# Schema.net
KiCad netlist of a schematic drawn in Altium Designer
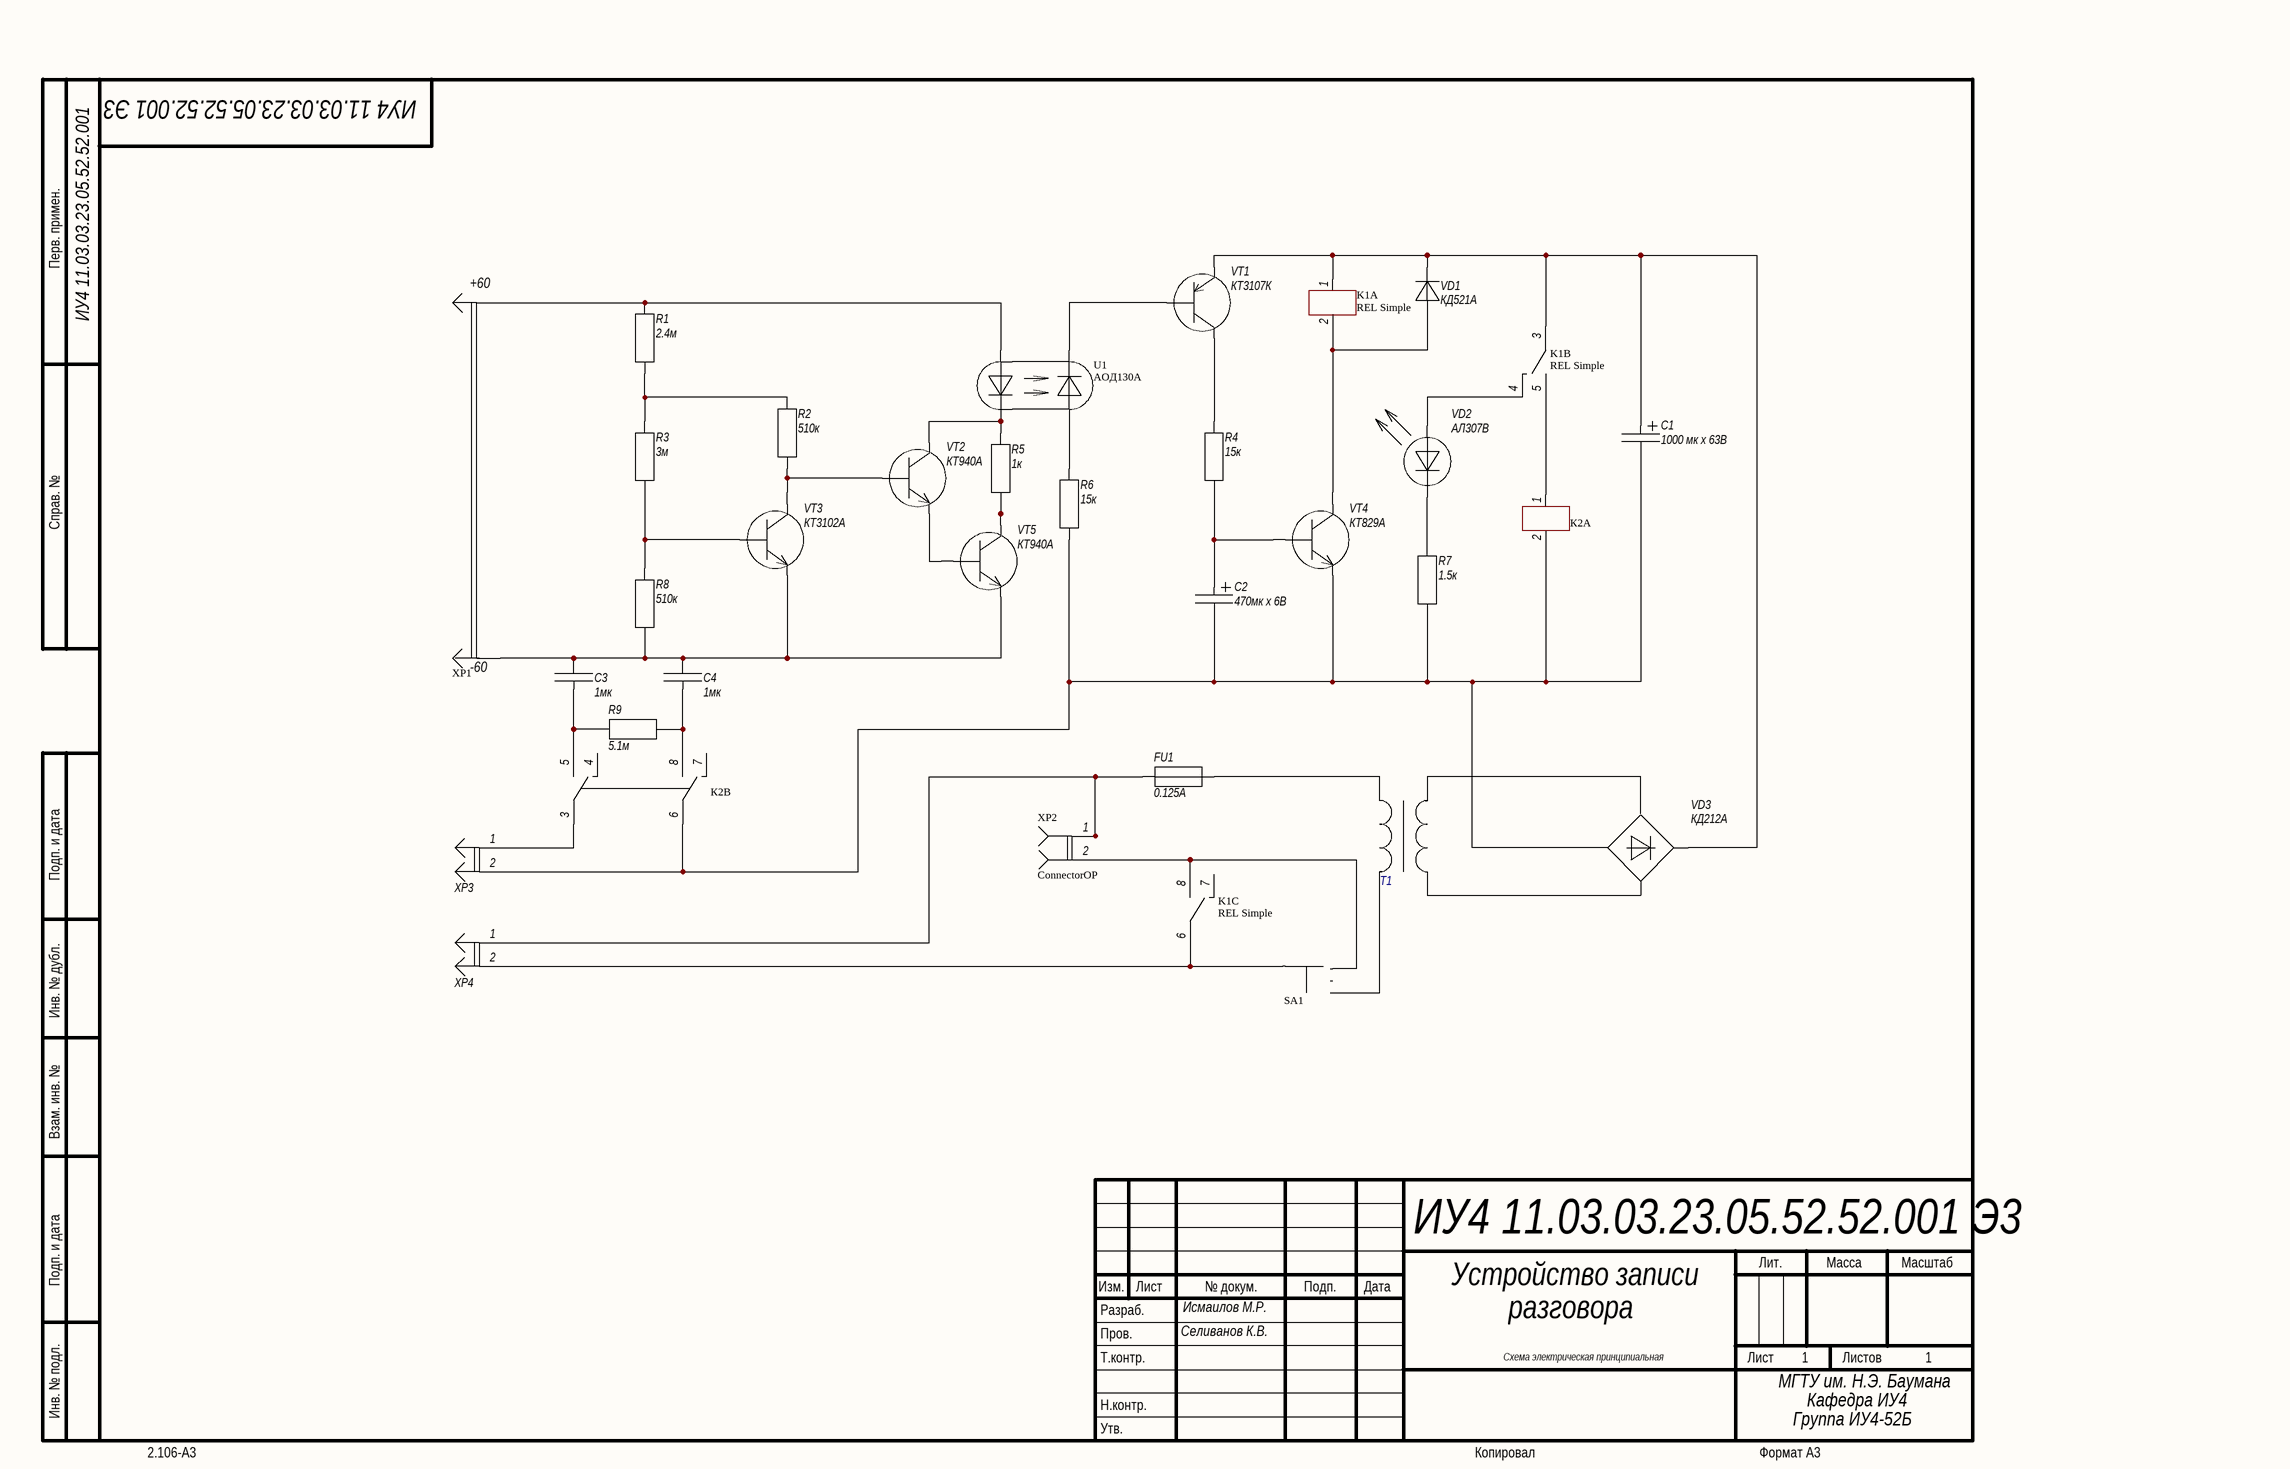
[diagram p0: Schema.SchDoc]

(export (version "E")
  (design (tool "Eeschema 10.0.6"))
  (components
    (comp (ref "C1")
      (value "1000 мк х 63В")
      (footprint "CAPPR1000-2300X4200")
      (libsource (lib "TKS Semestr") (part "CapPol 1000 мк х 63В"))
    )
    (comp (ref "C2")
      (value "470мк х 6В")
      (footprint "CAPPR1000-3600X5200")
      (libsource (lib "TKS Semestr") (part "CapPol 470мк х 6В"))
    )
    (comp (ref "C3")
      (value "1мк")
      (footprint "CAPRB_MURATA_DEBE33D103ZA3B")
      (libsource (lib "TKS Semestr") (part "Cap"))
    )
    (comp (ref "C4")
      (value "1мк")
      (footprint "CAPRB_MURATA_DEBE33D103ZA3B")
      (libsource (lib "TKS Semestr") (part "Cap"))
    )
    (comp (ref "FU1")
      (value "0.125А")
      (footprint "FUSH_SCHURTER_OGN")
      (libsource (lib "TKS Semestr") (part "Fuse 0.125А"))
    )
    (comp (ref "K1") (value "REL Simple") (footprint "USSR relay") (libsource (lib "") (part "REL Simple_1")))
    (comp (ref "R1")
      (value "2.4м")
      (footprint "RES2032-1400X350")
      (libsource (lib "TKS Semestr") (part "res 2.4м 2Вт"))
    )
    (comp (ref "R2")
      (value "510к")
      (footprint "RES2032-1400X350")
      (libsource (lib "TKS Semestr") (part "res 510к 2Вт"))
    )
    (comp (ref "R3")
      (value "3м")
      (footprint "RES2032-1400X350")
      (libsource (lib "TKS Semestr") (part "res 3м 2Вт"))
    )
    (comp (ref "R4")
      (value "15к")
      (footprint "RES2032-1400X350")
      (libsource (lib "TKS Semestr") (part "res 15к 2Вт"))
    )
    (comp (ref "R5")
      (value "1к")
      (footprint "RES2032-1400X350")
      (libsource (lib "TKS Semestr") (part "res 1к 2Вт"))
    )
    (comp (ref "R6")
      (value "15к")
      (footprint "RES2032-1400X350")
      (libsource (lib "TKS Semestr") (part "res 15к 2Вт"))
    )
    (comp (ref "R7")
      (value "1.5к")
      (footprint "RES2032-1400X350")
      (libsource (lib "TKS Semestr") (part "res 1.5к 2Вт"))
    )
    (comp (ref "R8")
      (value "510к")
      (footprint "RES2032-1400X350")
      (libsource (lib "TKS Semestr") (part "res 510к 2Вт"))
    )
    (comp (ref "R9")
      (value "5.1м")
      (footprint "RES2032-1400X350")
      (libsource (lib "TKS Semestr") (part "res 5.1м 2Вт"))
    )
    (comp (ref "SA1")
      (value "3-positoin switch")
      (footprint "SW_NR01103ANG13-1C")
      (libsource (lib "TKS Semestr") (part "3-positoin switch"))
    )
    (comp (ref "T1") (value "~") (libsource (lib "TKS Semestr") (part "TRANSFORMATOR-2")))
    (comp (ref "U1")
      (value "АОД130А")
      (footprint "DIP1016W50P254L458H480Q4")
      (libsource (lib "TKS Semestr") (part "opt АОД130А"))
    )
    (comp (ref "VD1")
      (value "КД521А")
      (footprint "DO-35")
      (libsource (lib "TKS Semestr") (part "DIODE КД521А"))
    )
    (comp (ref "VD2")
      (value "АЛ307В")
      (footprint "LED_3MM_GREEN_1C-2A")
      (libsource (lib "TKS Semestr") (part "LED АЛ307В"))
    )
    (comp (ref "VD3")
      (value "КД212А")
      (footprint "DIOB_GBJ2506")
      (libsource (lib "TKS Semestr") (part "BRIDGE"))
    )
    (comp (ref "VT1")
      (value "КТ3107К")
      (footprint "TO-92AA-P152")
      (libsource (lib "TKS Semestr") (part "КТ3107К"))
    )
    (comp (ref "VT2") (value "КТ940А") (footprint "TO-126-v") (libsource (lib "TKS Semestr") (part "КТ940А")))
    (comp (ref "VT3") (value "КТ3102А") (footprint "TO-18") (libsource (lib "TKS Semestr") (part "КТ3102А")))
    (comp (ref "VT4")
      (value "КТ829А")
      (footprint "TO-92AA-P152")
      (libsource (lib "TKS Semestr") (part "КТ829А"))
    )
    (comp (ref "VT5") (value "КТ940А") (footprint "TO-126-v") (libsource (lib "TKS Semestr") (part "КТ940А")))
    (comp (ref "XP1")
      (value "Connector2-long")
      (footprint "PHOENIX_1715721")
      (libsource (lib "TKS Semestr") (part "Connector Long"))
    )
    (comp (ref "XP2")
      (value "ConnectorOP")
      (footprint "PHOENIX_1715721")
      (libsource (lib "TKS Semestr") (part "ConnectorOP"))
    )
    (comp (ref "XP3")
      (value "~")
      (footprint "PHOENIX_1715721")
      (libsource (lib "TKS Semestr") (part "Connector Classic"))
    )
    (comp (ref "XP4")
      (value "~")
      (footprint "PHOENIX_1715721")
      (libsource (lib "TKS Semestr") (part "Connector Classic"))
    )
    (comp (ref "К2")
      (value "Rel2connected")
      (footprint "USSR relay")
      (libsource (lib "TKS Semestr") (part "Rel2connected"))
    )
  )
  (nets
    (net (code "1") (name "Net-(C1-Pad2)") (class "Default")
      (node (ref "C1") (pin "2") (pinfunction "2_2") (pintype "passive"))
      (node (ref "C2") (pin "2") (pinfunction "2_2") (pintype "passive"))
      (node (ref "R6") (pin "2") (pinfunction "2_2") (pintype "passive"))
      (node (ref "R7") (pin "2") (pinfunction "2_2") (pintype "passive"))
      (node (ref "VD3") (pin "4") (pinfunction "4_4") (pintype "passive"))
      (node (ref "VT4") (pin "1") (pinfunction "1_1") (pintype "passive"))
      (node (ref "XP3") (pin "2") (pinfunction "2_2") (pintype "passive"))
      (node (ref "К2") (pin "2") (pinfunction "2_2") (pintype "passive"))
      (node (ref "К2") (pin "6") (pinfunction "11_6") (pintype "passive"))
    )
    (net (code "2") (name "Net-(C2-Pad1)") (class "Default")
      (node (ref "C2") (pin "1") (pinfunction "1_1") (pintype "passive"))
      (node (ref "R4") (pin "2") (pinfunction "2_2") (pintype "passive"))
      (node (ref "VT4") (pin "2") (pinfunction "2_2") (pintype "passive"))
    )
    (net (code "3") (name "Net-(C3-Pad1)") (class "Default")
      (node (ref "C3") (pin "1") (pinfunction "1_1") (pintype "passive"))
      (node (ref "R9") (pin "2") (pinfunction "2_2") (pintype "passive"))
      (node (ref "К2") (pin "5") (pinfunction "14_5") (pintype "passive"))
    )
    (net (code "4") (name "Net-(C4-Pad1)") (class "Default")
      (node (ref "C4") (pin "1") (pinfunction "1_1") (pintype "passive"))
      (node (ref "R9") (pin "1") (pinfunction "1_1") (pintype "passive"))
      (node (ref "К2") (pin "8") (pinfunction "14_8") (pintype "passive"))
    )
    (net (code "5") (name "Net-(FU1-Pad1)") (class "Default")
      (node (ref "FU1") (pin "1") (pinfunction "1_1") (pintype "passive"))
      (node (ref "XP2") (pin "1") (pinfunction "1_1") (pintype "passive"))
      (node (ref "XP4") (pin "1") (pinfunction "1_1") (pintype "passive"))
    )
    (net (code "6") (name "Net-(FU1-Pad2)") (class "Default")
      (node (ref "FU1") (pin "2") (pinfunction "2_2") (pintype "passive"))
      (node (ref "T1") (pin "2") (pinfunction "2_2") (pintype "passive"))
    )
    (net (code "7") (name "Net-(K1-Pad5)") (class "Default")
      (node (ref "K1") (pin "5") (pinfunction "5_5") (pintype "passive"))
      (node (ref "К2") (pin "1") (pinfunction "1_1") (pintype "passive"))
    )
    (net (code "8") (name "Net-(R1-Pad2)") (class "Default")
      (node (ref "R1") (pin "2") (pinfunction "2_2") (pintype "passive"))
      (node (ref "R2") (pin "1") (pinfunction "1_1") (pintype "passive"))
      (node (ref "R3") (pin "1") (pinfunction "1_1") (pintype "passive"))
    )
    (net (code "9") (name "Net-(R2-Pad2)") (class "Default")
      (node (ref "R2") (pin "2") (pinfunction "2_2") (pintype "passive"))
      (node (ref "VT2") (pin "2") (pinfunction "2_2") (pintype "passive"))
      (node (ref "VT3") (pin "3") (pinfunction "3_3") (pintype "passive"))
    )
    (net (code "10") (name "Net-(R3-Pad2)") (class "Default")
      (node (ref "R3") (pin "2") (pinfunction "2_2") (pintype "passive"))
      (node (ref "R8") (pin "1") (pinfunction "1_1") (pintype "passive"))
      (node (ref "VT3") (pin "2") (pinfunction "2_2") (pintype "passive"))
    )
    (net (code "11") (name "Net-(R4-Pad1)") (class "Default")
      (node (ref "R4") (pin "1") (pinfunction "1_1") (pintype "passive"))
      (node (ref "VT1") (pin "3") (pinfunction "3_3") (pintype "passive"))
    )
    (net (code "12") (name "Net-(R5-Pad1)") (class "Default")
      (node (ref "R5") (pin "1") (pinfunction "1_1") (pintype "passive"))
      (node (ref "U1") (pin "1") (pinfunction "1_1") (pintype "passive"))
      (node (ref "VT2") (pin "1") (pinfunction "1_1") (pintype "passive"))
    )
    (net (code "13") (name "Net-(R5-Pad2)") (class "Default")
      (node (ref "R5") (pin "2") (pinfunction "2_2") (pintype "passive"))
      (node (ref "VT5") (pin "1") (pinfunction "1_1") (pintype "passive"))
    )
    (net (code "14") (name "Net-(R6-Pad1)") (class "Default")
      (node (ref "R6") (pin "1") (pinfunction "1_1") (pintype "passive"))
      (node (ref "U1") (pin "2") (pinfunction "2_2") (pintype "passive"))
    )
    (net (code "15") (name "Net-(SA1-0)") (class "Default")
      (node (ref "K1") (pin "6") (pinfunction "6_6") (pintype "passive"))
      (node (ref "SA1") (pin "1") (pinfunction "0_1") (pintype "passive"))
      (node (ref "XP4") (pin "2") (pinfunction "2_2") (pintype "passive"))
    )
    (net (code "16") (name "Net-(SA1-1)") (class "Default")
      (node (ref "K1") (pin "8") (pinfunction "8_8") (pintype "passive"))
      (node (ref "SA1") (pin "2") (pinfunction "1_2") (pintype "passive"))
      (node (ref "XP2") (pin "2") (pinfunction "2_2") (pintype "passive"))
    )
    (net (code "17") (name "Net-(SA1-3)") (class "Default")
      (node (ref "SA1") (pin "4") (pinfunction "3_4") (pintype "passive"))
      (node (ref "T1") (pin "1") (pinfunction "1_1") (pintype "passive"))
    )
    (net (code "18") (name "Net-(T1-Pad3)") (class "Default")
      (node (ref "T1") (pin "3") (pinfunction "3_3") (pintype "passive"))
      (node (ref "VD3") (pin "3") (pinfunction "3_3") (pintype "passive"))
    )
    (net (code "19") (name "Net-(T1-Pad4)") (class "Default")
      (node (ref "T1") (pin "4") (pinfunction "4_4") (pintype "passive"))
      (node (ref "VD3") (pin "2") (pinfunction "2_2") (pintype "passive"))
    )
    (net (code "20") (name "Net-(U1-Pad3)") (class "Default")
      (node (ref "U1") (pin "3") (pinfunction "3_3") (pintype "passive"))
      (node (ref "VT1") (pin "2") (pinfunction "2_2") (pintype "passive"))
    )
    (net (code "21") (name "Net-(VD1-A)") (class "Default")
      (node (ref "K1") (pin "2") (pinfunction "2_2") (pintype "passive"))
      (node (ref "VD1") (pin "1") (pinfunction "A_1") (pintype "passive"))
      (node (ref "VT4") (pin "3") (pinfunction "3_3") (pintype "passive"))
    )
    (net (code "22") (name "Net-(VD1-C)") (class "Default")
      (node (ref "C1") (pin "1") (pinfunction "1_1") (pintype "passive"))
      (node (ref "K1") (pin "1") (pinfunction "1_1") (pintype "passive"))
      (node (ref "K1") (pin "3") (pinfunction "3_3") (pintype "passive"))
      (node (ref "VD1") (pin "2") (pinfunction "C_2") (pintype "passive"))
      (node (ref "VD3") (pin "1") (pinfunction "1_1") (pintype "passive"))
      (node (ref "VT1") (pin "1") (pinfunction "1_1") (pintype "passive"))
    )
    (net (code "23") (name "Net-(VD2-A)") (class "Default")
      (node (ref "K1") (pin "4") (pinfunction "4_4") (pintype "passive"))
      (node (ref "VD2") (pin "1") (pinfunction "A_1") (pintype "passive"))
    )
    (net (code "24") (name "Net-(VD2-C)") (class "Default")
      (node (ref "R7") (pin "1") (pinfunction "1_1") (pintype "passive"))
      (node (ref "VD2") (pin "2") (pinfunction "C_2") (pintype "passive"))
    )
    (net (code "25") (name "Net-(VT2-Pad3)") (class "Default")
      (node (ref "VT2") (pin "3") (pinfunction "3_3") (pintype "passive"))
      (node (ref "VT5") (pin "2") (pinfunction "2_2") (pintype "passive"))
    )
    (net (code "26") (name "Net-(XP1-+60)") (class "Default")
      (node (ref "C3") (pin "2") (pinfunction "2_2") (pintype "passive"))
      (node (ref "C4") (pin "2") (pinfunction "2_2") (pintype "passive"))
      (node (ref "R8") (pin "2") (pinfunction "2_2") (pintype "passive"))
      (node (ref "VT3") (pin "1") (pinfunction "1_1") (pintype "passive"))
      (node (ref "VT5") (pin "3") (pinfunction "3_3") (pintype "passive"))
      (node (ref "XP1") (pin "2") (pinfunction "+60_2") (pintype "passive"))
    )
    (net (code "27") (name "Net-(XP1--60)") (class "Default")
      (node (ref "R1") (pin "1") (pinfunction "1_1") (pintype "passive"))
      (node (ref "U1") (pin "4") (pinfunction "4_4") (pintype "passive"))
      (node (ref "XP1") (pin "1") (pinfunction "-60_1") (pintype "passive"))
    )
    (net (code "28") (name "Net-(XP3-Pad1)") (class "Default")
      (node (ref "XP3") (pin "1") (pinfunction "1_1") (pintype "passive"))
      (node (ref "К2") (pin "3") (pinfunction "11_3") (pintype "passive"))
    )
    (net (code "29") (name "unconnected-(K1-Pad7)") (class "Default")
      (node (ref "K1") (pin "7") (pinfunction "7_7") (pintype "passive"))
    )
    (net (code "30") (name "unconnected-(SA1-2-Pad3)") (class "Default")
      (node (ref "SA1") (pin "3") (pinfunction "2_3") (pintype "passive"))
    )
    (net (code "31") (name "unconnected-(К2B-12-Pad4)") (class "Default")
      (node (ref "К2") (pin "4") (pinfunction "12_4") (pintype "passive"))
    )
    (net (code "32") (name "unconnected-(К2B-12-Pad7)") (class "Default")
      (node (ref "К2") (pin "7") (pinfunction "12_7") (pintype "passive"))
    )
  )
)
